# v1_0.net
KiCad netlist of a schematic drawn in Altium Designer
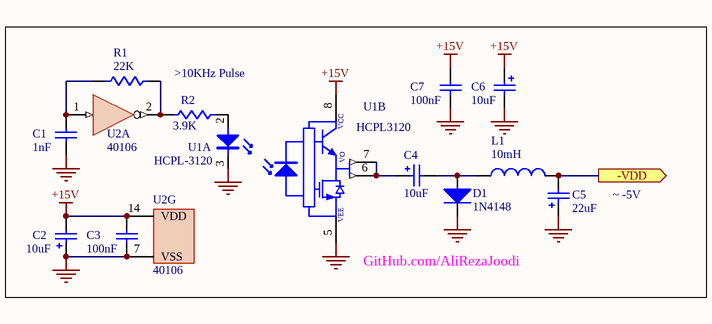
[diagram p0: v1.0.SchDoc]

(export (version "E")
  (design (tool "Eeschema 10.0.6"))
  (components
    (comp (ref "C1")
      (value "1nF")
      (footprint "CAPNTO2.54-3.05x1.78A")
      (description "Capacitor")
      (fields
        (field (name "MANUFACTURER") "Generic Components")
        (field (name "Comment") "Cap")
        (field (name "PUBLISHER") "Altium Limited")
      )
      (libsource (lib "Miscellaneous Devices") (part "Cap"))
    )
    (comp (ref "C2")
      (value "10uF")
      (footprint "CAPPR2.5-6.3x5")
      (description "Polarized Capacitor (Radial)")
      (fields (field (name "MANUFACTURER") "Generic Components") (field (name "PUBLISHER") "Altium Limited"))
      (libsource (lib "Miscellaneous Devices") (part "Cap Pol1"))
    )
    (comp (ref "C3")
      (value "100nF")
      (footprint "CAPNTO2.54-3.05x1.78A")
      (description "Capacitor")
      (fields (field (name "MANUFACTURER") "Generic Components") (field (name "PUBLISHER") "Altium Limited"))
      (libsource (lib "Miscellaneous Devices") (part "Cap"))
    )
    (comp (ref "C4")
      (value "10uF")
      (footprint "CAPPR2.5-6.3x5")
      (description "Polarized Capacitor (Radial)")
      (fields
        (field (name "MANUFACTURER") "Generic Components")
        (field (name "Comment") "Cap Pol1")
        (field (name "PUBLISHER") "Altium Limited")
      )
      (libsource (lib "Miscellaneous Devices") (part "Cap Pol1"))
    )
    (comp (ref "C5")
      (value "22uF")
      (footprint "CAPPR2.5-6.3x5")
      (description "Polarized Capacitor (Radial)")
      (fields (field (name "MANUFACTURER") "Generic Components") (field (name "PUBLISHER") "Altium Limited"))
      (libsource (lib "Miscellaneous Devices") (part "Cap Pol1"))
    )
    (comp (ref "C6")
      (value "10uF")
      (footprint "CAPPR2.5-6.3x5")
      (description "Polarized Capacitor (Radial)")
      (fields (field (name "MANUFACTURER") "Generic Components") (field (name "PUBLISHER") "Altium Limited"))
      (libsource (lib "Miscellaneous Devices") (part "Cap Pol1"))
    )
    (comp (ref "C7")
      (value "100nF")
      (footprint "CAPNTO2.54-3.05x1.78A")
      (description "Capacitor")
      (fields (field (name "MANUFACTURER") "Generic Components") (field (name "PUBLISHER") "Altium Limited"))
      (libsource (lib "Miscellaneous Devices") (part "Cap"))
    )
    (comp (ref "D1")
      (value "1N4148")
      (footprint "DIODE-0.4")
      (description "Default Diode")
      (fields
        (field (name "MANUFACTURER") "Generic Components")
        (field (name "Comment") "Diode")
        (field (name "PUBLISHER") "Altium Limited")
      )
      (libsource (lib "Miscellaneous Devices") (part "Diode"))
    )
    (comp (ref "L1")
      (value "10mH")
      (footprint "INDUCTOR-2V")
      (description "Inductor")
      (fields (field (name "PUBLISHER") "Altium Limited"))
      (libsource (lib "Miscellaneous Devices") (part "Inductor"))
    )
    (comp (ref "R1")
      (value "22K")
      (footprint "AXIAL-0.4")
      (description "Resistor")
      (fields (field (name "MANUFACTURER") "Generic Components") (field (name "PUBLISHER") "Altium Limited"))
      (libsource (lib "Miscellaneous Devices") (part "Res1"))
    )
    (comp (ref "R2")
      (value "3.9K")
      (footprint "AXIAL-0.4")
      (description "Resistor")
      (fields (field (name "MANUFACTURER") "Generic Components") (field (name "PUBLISHER") "Altium Limited"))
      (libsource (lib "Miscellaneous Devices") (part "Res1"))
    )
    (comp (ref "U1")
      (value "HCPL-3120")
      (footprint "DIP8")
      (libsource (lib "my Libraries") (part "HCPL-3120"))
    )
    (comp (ref "U2")
      (value "40106")
      (footprint "DIP_14")
      (description "Hex inverting Schmitt trigger, 14-Pin")
      (fields (field (name "PUBLISHER") "Altium Limited"))
      (libsource (lib "Other_Myself") (part "40106"))
    )
  )
  (nets
    (net (code "1") (name "+15V") (class "Default")
      (node (ref "C2") (pin "2") (pinfunction "2_2") (pintype "passive"))
      (node (ref "C3") (pin "2") (pinfunction "2_2") (pintype "passive"))
      (node (ref "C6") (pin "1") (pinfunction "1_1") (pintype "passive"))
      (node (ref "C7") (pin "2") (pinfunction "2_2") (pintype "passive"))
      (node (ref "U1") (pin "8") (pinfunction "VCC_8") (pintype "power_in"))
      (node (ref "U2") (pin "14") (pinfunction "VDD_14") (pintype "passive"))
    )
    (net (code "2") (name "/-VDD") (class "Default")
      (node (ref "C5") (pin "2") (pinfunction "2_2") (pintype "passive"))
      (node (ref "L1") (pin "2") (pinfunction "2_2") (pintype "passive"))
    )
    (net (code "3") (name "GND") (class "Default")
      (node (ref "C1") (pin "2") (pinfunction "2_2") (pintype "passive"))
      (node (ref "C2") (pin "1") (pinfunction "1_1") (pintype "passive"))
      (node (ref "C3") (pin "1") (pinfunction "1_1") (pintype "passive"))
      (node (ref "C5") (pin "1") (pinfunction "1_1") (pintype "passive"))
      (node (ref "C6") (pin "2") (pinfunction "2_2") (pintype "passive"))
      (node (ref "C7") (pin "1") (pinfunction "1_1") (pintype "passive"))
      (node (ref "D1") (pin "2") (pinfunction "K_2") (pintype "passive"))
      (node (ref "U1") (pin "3") (pinfunction "K_3") (pintype "power_in"))
      (node (ref "U1") (pin "5") (pinfunction "VEE_5") (pintype "power_in"))
      (node (ref "U2") (pin "7") (pinfunction "VSS_7") (pintype "power_in"))
    )
    (net (code "4") (name "Net-(C4-Pad1)") (class "Default")
      (node (ref "C4") (pin "1") (pinfunction "1_1") (pintype "passive"))
      (node (ref "U1") (pin "6") (pinfunction "VO_6") (pintype "output"))
      (node (ref "U1") (pin "7") (pinfunction "VO_7") (pintype "output"))
    )
    (net (code "5") (name "Net-(D1-A)") (class "Default")
      (node (ref "C4") (pin "2") (pinfunction "2_2") (pintype "passive"))
      (node (ref "D1") (pin "1") (pinfunction "A_1") (pintype "passive"))
      (node (ref "L1") (pin "1") (pinfunction "1_1") (pintype "passive"))
    )
    (net (code "6") (name "Net-(U1A-A)") (class "Default")
      (node (ref "R2") (pin "2") (pinfunction "2_2") (pintype "passive"))
      (node (ref "U1") (pin "2") (pinfunction "A_2") (pintype "power_in"))
    )
    (net (code "7") (name "Net-(U2A-I)") (class "Default")
      (node (ref "C1") (pin "1") (pinfunction "1_1") (pintype "passive"))
      (node (ref "R1") (pin "2") (pinfunction "2_2") (pintype "passive"))
      (node (ref "U2") (pin "1") (pinfunction "I_1") (pintype "input"))
    )
    (net (code "8") (name "Net-(U2A-~{O})") (class "Default")
      (node (ref "R1") (pin "1") (pinfunction "1_1") (pintype "passive"))
      (node (ref "R2") (pin "1") (pinfunction "1_1") (pintype "passive"))
      (node (ref "U2") (pin "2") (pinfunction "~{O}_2") (pintype "output"))
    )
  )
)
